# main.net
KiCad netlist of a schematic drawn in Altium Designer
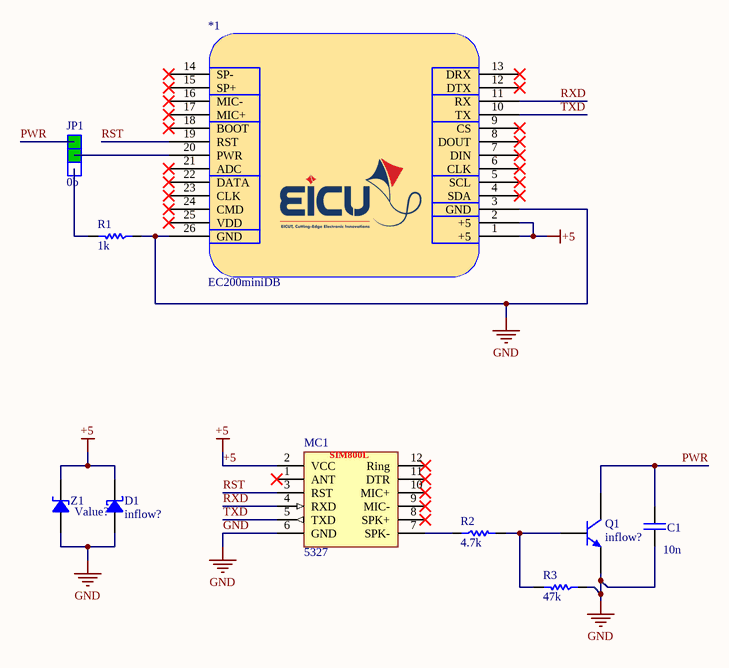
[diagram p0: main.SchDoc]

(export (version "E")
  (design (tool "Eeschema 10.0.6"))
  (components
    (comp (ref "*1")
      (value "EC200miniDB")
      (footprint "EC200mini - NO3D")
      (description "EICUT.com")
      (libsource (lib "EC200miniDB") (part "EC200miniDB"))
    )
    (comp (ref "C1")
      (value "10n")
      (footprint "CAP 1206/3216")
      (description "Bipolar ceramic capacitor SMD")
      (fields (field (name "VALIDATION") "Valid"))
      (libsource (lib "aKaReZa") (part "Cap_Multi_1u_50_1206"))
    )
    (comp (ref "D1")
      (value "SMBJ15A")
      (footprint "DO214AA SMB")
      (description "Transil diodes provide high overvoltage protection by clamping action")
      (fields (field (name "INFLOW") "inflow?") (field (name "VALIDATION") "Valid"))
      (libsource (lib "aKaReZa") (part "Semi_Diod_TVS_SMBJ15A"))
    )
    (comp (ref "JP1")
      (value "0b")
      (footprint "Jumper Selector SMD")
      (description "Jumper Selector")
      (fields (field (name "VALIDATION") "Valid"))
      (libsource (lib "aKaReZa") (part "SW_Other_JSelector_SMD"))
    )
    (comp (ref "MC1")
      (value "Sim800L")
      (footprint "Sim800L_Module - NO3D")
      (description "SimCom GSM/GPRS Module")
      (fields (field (name "INFLOW") "5327") (field (name "VALIDATION") "NT"))
      (libsource (lib "aKaReZa") (part "ModSen_Com_Sim800L"))
    )
    (comp (ref "Q1")
      (value "NPN")
      (footprint "SOT23_N")
      (description "NPN General purpose Transistor")
      (fields (field (name "INFLOW") "inflow?") (field (name "VALIDATION") "Valid"))
      (libsource (lib "aKaReZa") (part "Semi_BJT_BC817"))
    )
    (comp (ref "R1")
      (value "1k")
      (footprint "RES 1206 (3216X08L)")
      (description "Resistor")
      (fields (field (name "VALIDATION") "Valid"))
      (libsource (lib "aKaReZa") (part "Res_SMD_1206"))
    )
    (comp (ref "R2")
      (value "4.7k")
      (footprint "RES 1206 (3216X08L)")
      (description "Resistor")
      (fields (field (name "VALIDATION") "Valid"))
      (libsource (lib "aKaReZa") (part "Res_SMD_1206"))
    )
    (comp (ref "R3")
      (value "47k")
      (footprint "RES 1206 (3216X08L)")
      (description "Resistor")
      (fields (field (name "VALIDATION") "Valid"))
      (libsource (lib "aKaReZa") (part "Res_SMD_1206"))
    )
    (comp (ref "Z1")
      (value "Value?")
      (footprint "SOD80, LL-34")
      (description "Zener Diode")
      (fields (field (name "VALIDATION") "Valid"))
      (libsource (lib "aKaReZa") (part "Semi_Diod_Zener_SMD"))
    )
  )
  (nets
    (net (code "1") (name "+5") (class "Default")
      (node (ref "*1") (pin "1") (pinfunction "+5_1") (pintype "passive"))
      (node (ref "*1") (pin "2") (pinfunction "+5_2") (pintype "passive"))
      (node (ref "D1") (pin "2") (pinfunction "2_2") (pintype "passive"))
      (node (ref "MC1") (pin "2") (pinfunction "VCC_2") (pintype "power_in"))
      (node (ref "Z1") (pin "2") (pinfunction "2_2") (pintype "passive"))
    )
    (net (code "2") (name "/PWR") (class "Default")
      (node (ref "C1") (pin "1") (pinfunction "1_1") (pintype "passive"))
      (node (ref "JP1") (pin "1") (pinfunction "1_1") (pintype "passive"))
      (node (ref "Q1") (pin "3") (pinfunction "C_3") (pintype "passive"))
    )
    (net (code "3") (name "/RST") (class "Default")
      (node (ref "*1") (pin "19") (pinfunction "RST_19") (pintype "passive"))
      (node (ref "MC1") (pin "3") (pinfunction "RST_3") (pintype "passive"))
    )
    (net (code "4") (name "/RXD") (class "Default")
      (node (ref "*1") (pin "11") (pinfunction "RX_11") (pintype "passive"))
      (node (ref "MC1") (pin "4") (pinfunction "RXD_4") (pintype "input"))
    )
    (net (code "5") (name "/TXD") (class "Default")
      (node (ref "*1") (pin "10") (pinfunction "TX_10") (pintype "passive"))
      (node (ref "MC1") (pin "5") (pinfunction "TXD_5") (pintype "output"))
    )
    (net (code "6") (name "GND") (class "Default")
      (node (ref "*1") (pin "26") (pinfunction "GND_26") (pintype "passive"))
      (node (ref "*1") (pin "3") (pinfunction "GND_3") (pintype "passive"))
      (node (ref "C1") (pin "2") (pinfunction "2_2") (pintype "passive"))
      (node (ref "D1") (pin "1") (pinfunction "1_1") (pintype "passive"))
      (node (ref "MC1") (pin "6") (pinfunction "GND_6") (pintype "power_in"))
      (node (ref "Q1") (pin "2") (pinfunction "E_2") (pintype "passive"))
      (node (ref "R1") (pin "1") (pinfunction "1_1") (pintype "passive"))
      (node (ref "R3") (pin "1") (pinfunction "1_1") (pintype "passive"))
      (node (ref "Z1") (pin "1") (pinfunction "1_1") (pintype "passive"))
    )
    (net (code "7") (name "Net-(*1-PWR)") (class "Default")
      (node (ref "*1") (pin "20") (pinfunction "PWR_20") (pintype "passive"))
      (node (ref "JP1") (pin "2") (pinfunction "2_2") (pintype "passive"))
    )
    (net (code "8") (name "Net-(JP1-Pad3)") (class "Default")
      (node (ref "JP1") (pin "3") (pinfunction "3_3") (pintype "passive"))
      (node (ref "R1") (pin "2") (pinfunction "2_2") (pintype "passive"))
    )
    (net (code "9") (name "Net-(MC1-SPK-)") (class "Default")
      (node (ref "MC1") (pin "7") (pinfunction "SPK-_7") (pintype "passive"))
      (node (ref "R2") (pin "1") (pinfunction "1_1") (pintype "passive"))
    )
    (net (code "10") (name "Net-(Q1-B)") (class "Default")
      (node (ref "Q1") (pin "1") (pinfunction "B_1") (pintype "passive"))
      (node (ref "R2") (pin "2") (pinfunction "2_2") (pintype "passive"))
      (node (ref "R3") (pin "2") (pinfunction "2_2") (pintype "passive"))
    )
    (net (code "11") (name "unconnected-(*1-ADC-Pad21)") (class "Default")
      (node (ref "*1") (pin "21") (pinfunction "ADC_21") (pintype "passive+no_connect"))
    )
    (net (code "12") (name "unconnected-(*1-BOOT-Pad18)") (class "Default")
      (node (ref "*1") (pin "18") (pinfunction "BOOT_18") (pintype "passive+no_connect"))
    )
    (net (code "13") (name "unconnected-(*1-CLK-Pad6)") (class "Default")
      (node (ref "*1") (pin "6") (pinfunction "CLK_6") (pintype "passive+no_connect"))
    )
    (net (code "14") (name "unconnected-(*1-CLK-Pad23)") (class "Default")
      (node (ref "*1") (pin "23") (pinfunction "CLK_23") (pintype "passive+no_connect"))
    )
    (net (code "15") (name "unconnected-(*1-CMD-Pad24)") (class "Default")
      (node (ref "*1") (pin "24") (pinfunction "CMD_24") (pintype "passive+no_connect"))
    )
    (net (code "16") (name "unconnected-(*1-CS-Pad9)") (class "Default")
      (node (ref "*1") (pin "9") (pinfunction "CS_9") (pintype "passive+no_connect"))
    )
    (net (code "17") (name "unconnected-(*1-DATA-Pad22)") (class "Default")
      (node (ref "*1") (pin "22") (pinfunction "DATA_22") (pintype "passive+no_connect"))
    )
    (net (code "18") (name "unconnected-(*1-DIN-Pad7)") (class "Default")
      (node (ref "*1") (pin "7") (pinfunction "DIN_7") (pintype "passive+no_connect"))
    )
    (net (code "19") (name "unconnected-(*1-DOUT-Pad8)") (class "Default")
      (node (ref "*1") (pin "8") (pinfunction "DOUT_8") (pintype "passive+no_connect"))
    )
    (net (code "20") (name "unconnected-(*1-DRX-Pad13)") (class "Default")
      (node (ref "*1") (pin "13") (pinfunction "DRX_13") (pintype "passive+no_connect"))
    )
    (net (code "21") (name "unconnected-(*1-DTX-Pad12)") (class "Default")
      (node (ref "*1") (pin "12") (pinfunction "DTX_12") (pintype "passive+no_connect"))
    )
    (net (code "22") (name "unconnected-(*1-MIC+-Pad17)") (class "Default")
      (node (ref "*1") (pin "17") (pinfunction "MIC+_17") (pintype "passive+no_connect"))
    )
    (net (code "23") (name "unconnected-(*1-MIC--Pad16)") (class "Default")
      (node (ref "*1") (pin "16") (pinfunction "MIC-_16") (pintype "passive+no_connect"))
    )
    (net (code "24") (name "unconnected-(*1-SCL-Pad5)") (class "Default")
      (node (ref "*1") (pin "5") (pinfunction "SCL_5") (pintype "passive+no_connect"))
    )
    (net (code "25") (name "unconnected-(*1-SDA-Pad4)") (class "Default")
      (node (ref "*1") (pin "4") (pinfunction "SDA_4") (pintype "passive+no_connect"))
    )
    (net (code "26") (name "unconnected-(*1-SP+-Pad15)") (class "Default")
      (node (ref "*1") (pin "15") (pinfunction "SP+_15") (pintype "passive+no_connect"))
    )
    (net (code "27") (name "unconnected-(*1-SP--Pad14)") (class "Default")
      (node (ref "*1") (pin "14") (pinfunction "SP-_14") (pintype "passive+no_connect"))
    )
    (net (code "28") (name "unconnected-(*1-VDD-Pad25)") (class "Default")
      (node (ref "*1") (pin "25") (pinfunction "VDD_25") (pintype "passive+no_connect"))
    )
    (net (code "29") (name "unconnected-(MC1-ANT-Pad1)") (class "Default")
      (node (ref "MC1") (pin "1") (pinfunction "ANT_1") (pintype "passive+no_connect"))
    )
    (net (code "30") (name "unconnected-(MC1-DTR-Pad11)") (class "Default")
      (node (ref "MC1") (pin "11") (pinfunction "DTR_11") (pintype "passive+no_connect"))
    )
    (net (code "31") (name "unconnected-(MC1-MIC+-Pad10)") (class "Default")
      (node (ref "MC1") (pin "10") (pinfunction "MIC+_10") (pintype "passive+no_connect"))
    )
    (net (code "32") (name "unconnected-(MC1-MIC--Pad9)") (class "Default")
      (node (ref "MC1") (pin "9") (pinfunction "MIC-_9") (pintype "passive+no_connect"))
    )
    (net (code "33") (name "unconnected-(MC1-Ring-Pad12)") (class "Default")
      (node (ref "MC1") (pin "12") (pinfunction "Ring_12") (pintype "passive+no_connect"))
    )
    (net (code "34") (name "unconnected-(MC1-SPK+-Pad8)") (class "Default")
      (node (ref "MC1") (pin "8") (pinfunction "SPK+_8") (pintype "passive+no_connect"))
    )
  )
)
